# Morpheus_NDO_ANO.net
KiCad netlist of a schematic drawn in Altium Designer
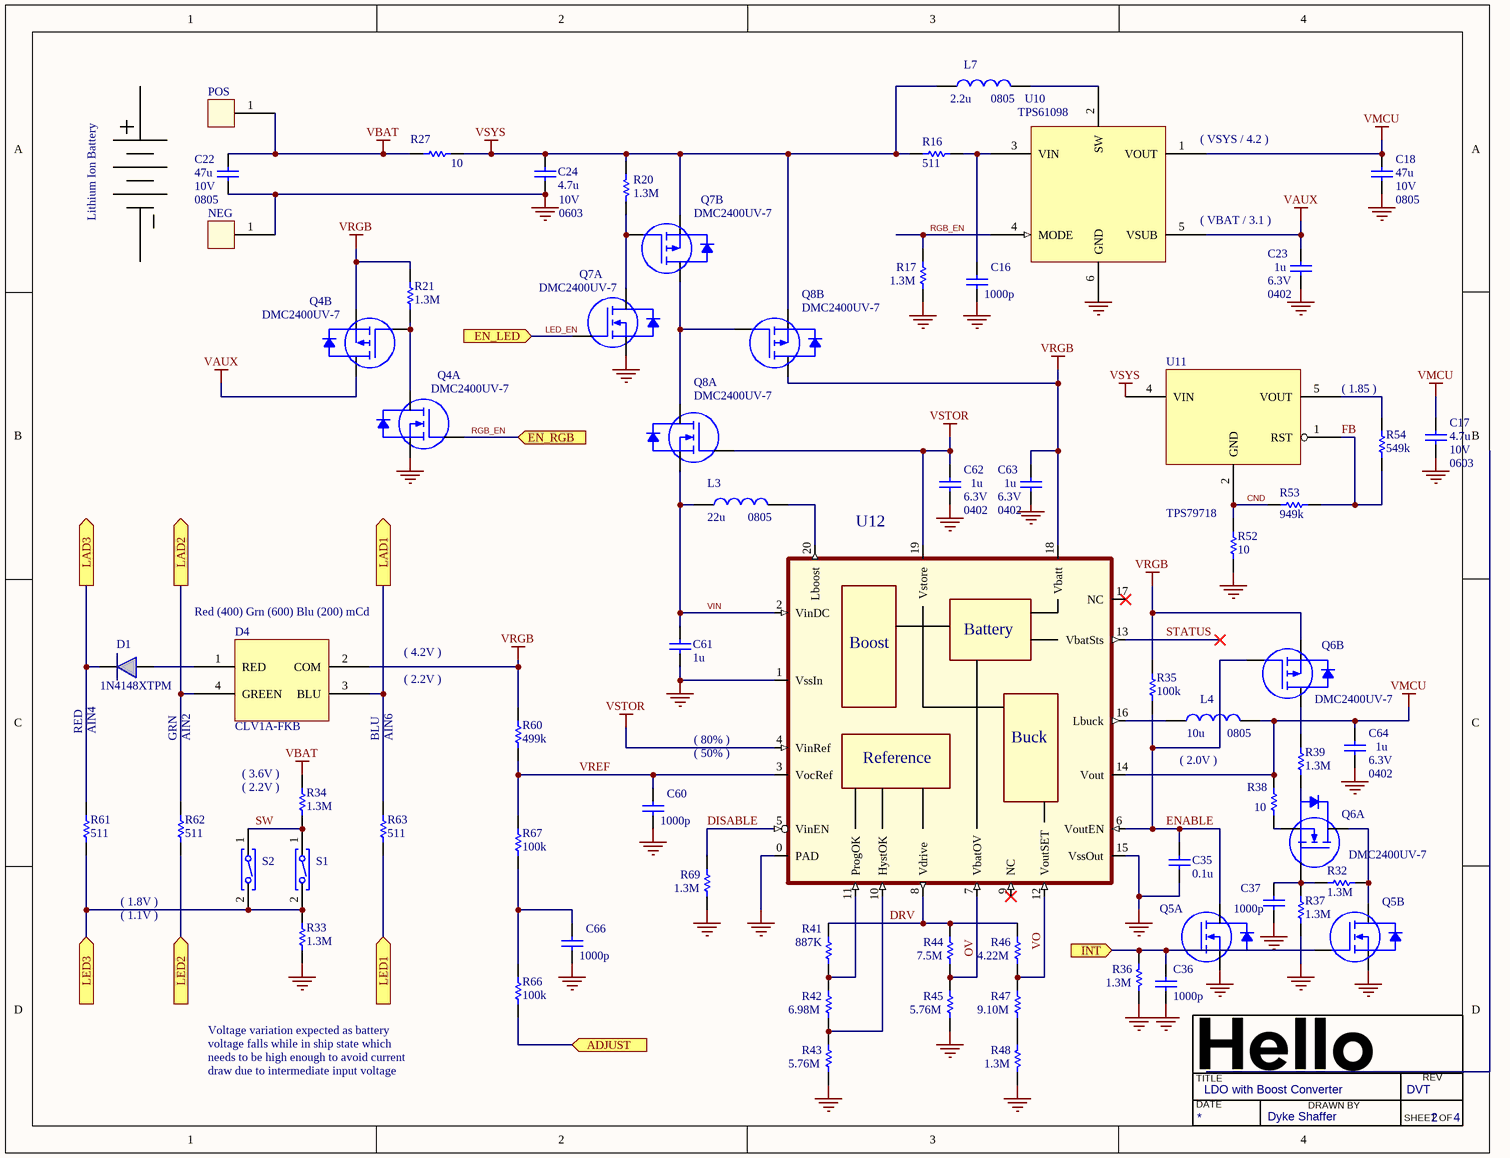
[diagram p0: Morpheus_NDO_ANO.SchDoc]

(export (version "E")
  (design (tool "Eeschema 10.0.6"))
  (components
    (comp (ref "C16")
      (value "1000p")
      (footprint "0402C20X24")
      (description "Chip capacitor")
      (fields (field (name "TOLERANCE") "10%") (field (name "VOLTAGE") "50V"))
      (libsource (lib "Hello") (part "C_1000p_10_50_X7R_0402"))
    )
    (comp (ref "C17")
      (value "4.7u")
      (footprint "CAP0603_SENSE_DVT")
      (description "Chip capacitor")
      (fields (field (name "SIZE") "0603") (field (name "TOLERANCE") "20%") (field (name "VOLTAGE") "10V"))
      (libsource (lib "Hello") (part "C_4.7u_20_10_X5R_0603"))
    )
    (comp (ref "C18")
      (value "47u")
      (footprint "0805C45X55")
      (description "Chip capacitor")
      (fields (field (name "SIZE") "0805") (field (name "TOLERANCE") "20%") (field (name "VOLTAGE") "10V"))
      (libsource (lib "Hello") (part "C_47u_20_10_X5R_0805"))
    )
    (comp (ref "C22")
      (value "47u")
      (footprint "CAP0805_SENSE_DVT")
      (description "Chip capacitor")
      (fields (field (name "SIZE") "0805") (field (name "TOLERANCE") "20%") (field (name "VOLTAGE") "10V"))
      (libsource (lib "Hello") (part "C_47u_20_10_X5R_0805"))
    )
    (comp (ref "C23")
      (value "1u")
      (footprint "CAP0402_SENSE_DVT")
      (description "Chip capacitor")
      (fields (field (name "SIZE") "0402") (field (name "TOLERANCE") "10%") (field (name "VOLTAGE") "6.3V"))
      (libsource (lib "Hello") (part "C_1u_10_6.3_X5R_0402"))
    )
    (comp (ref "C24")
      (value "4.7u")
      (footprint "CAP0603_SENSE_DVT")
      (description "Chip capacitor")
      (fields (field (name "SIZE") "0603") (field (name "TOLERANCE") "20%") (field (name "VOLTAGE") "10V"))
      (libsource (lib "Hello") (part "C_4.7u_20_10_X5R_0603"))
    )
    (comp (ref "C35")
      (value "0.1u")
      (footprint "CAP0402_SENSE_DVT")
      (description "Chip capacitor")
      (fields (field (name "TOLERANCE") "10%") (field (name "VOLTAGE") "50V"))
      (libsource (lib "Hello") (part "C_0.1u_10_50_X7R_0402"))
    )
    (comp (ref "C36")
      (value "1000p")
      (footprint "0402C20X24")
      (description "Chip capacitor")
      (fields (field (name "TOLERANCE") "10%") (field (name "VOLTAGE") "50V"))
      (libsource (lib "Hello") (part "C_1000p_10_50_X7R_0402"))
    )
    (comp (ref "C37")
      (value "1000p")
      (footprint "0402C20X24")
      (description "Chip capacitor")
      (fields (field (name "TOLERANCE") "10%") (field (name "VOLTAGE") "50V"))
      (libsource (lib "Hello") (part "C_1000p_10_50_X7R_0402"))
    )
    (comp (ref "C60")
      (value "1000p")
      (footprint "0402C20X24")
      (description "Chip capacitor")
      (fields (field (name "TOLERANCE") "10%") (field (name "VOLTAGE") "50V"))
      (libsource (lib "Hello") (part "C_1000p_10_50_X7R_0402"))
    )
    (comp (ref "C61")
      (value "1u")
      (footprint "CAP0402_SENSE_DVT")
      (description "Chip capacitor")
      (fields (field (name "TOLERANCE") "10%") (field (name "VOLTAGE") "6.3V"))
      (libsource (lib "Hello") (part "C_1u_10_6.3_X5R_0402"))
    )
    (comp (ref "C62")
      (value "1u")
      (footprint "CAP0402_SENSE_DVT")
      (description "Chip capacitor")
      (fields (field (name "SIZE") "0402") (field (name "TOLERANCE") "10%") (field (name "VOLTAGE") "6.3V"))
      (libsource (lib "Hello") (part "C_1u_10_6.3_X5R_0402"))
    )
    (comp (ref "C63")
      (value "1u")
      (footprint "CAP0402_SENSE_DVT")
      (description "Chip capacitor")
      (fields (field (name "SIZE") "0402") (field (name "TOLERANCE") "10%") (field (name "VOLTAGE") "6.3V"))
      (libsource (lib "Hello") (part "C_1u_10_6.3_X5R_0402"))
    )
    (comp (ref "C64")
      (value "1u")
      (footprint "CAP0402_SENSE_DVT")
      (description "Chip capacitor")
      (fields (field (name "SIZE") "0402") (field (name "TOLERANCE") "10%") (field (name "VOLTAGE") "6.3V"))
      (libsource (lib "Hello") (part "C_1u_10_6.3_X5R_0402"))
    )
    (comp (ref "C66")
      (value "1000p")
      (footprint "0402C20X24")
      (description "Chip capacitor")
      (fields (field (name "TOLERANCE") "10%") (field (name "VOLTAGE") "50V"))
      (libsource (lib "Hello") (part "C_1000p_10_50_X7R_0402"))
    )
    (comp (ref "D1")
      (value "1N4148XTPM")
      (footprint "SOD523")
      (description "Silicon diode, 30V 200mA")
      (libsource (lib "Hello") (part "1N4148XTPM"))
    )
    (comp (ref "D4")
      (value "Red (400) Grn (600) Blu (200) mCd")
      (footprint "PLCC150X290P280X320X190-4")
      (description "RGB LED Array")
      (fields (field (name "PN") "CLV1A-FKB") (field (name "Comment") "CLV1A-FKB"))
      (libsource (lib "Hello") (part "CLV1A-FKB"))
    )
    (comp (ref "L3")
      (value "22u")
      (footprint "IND_0805")
      (description "SMD power inductor, 22uH")
      (fields (field (name "TOLERANCE") "20%") (field (name "SIZE") "0805"))
      (libsource (lib "Morpheus_pill") (part "L_22u_0805"))
    )
    (comp (ref "L4")
      (value "10u")
      (footprint "IND_0805")
      (description "SMD power inductor, 10uH")
      (fields (field (name "TOLERANCE") "20%") (field (name "SIZE") "0805"))
      (libsource (lib "Morpheus_pill") (part "L_10u_0805"))
    )
    (comp (ref "L7")
      (value "2.2u")
      (footprint "IND_0805")
      (description "SMD power inductor, 2.2uH")
      (fields (field (name "TOLERANCE") "20%") (field (name "SIZE") "0805"))
      (libsource (lib "Morpheus_pill") (part "L_2.2u_0805"))
    )
    (comp (ref "NEG")
      (value "~")
      (footprint "TP50x50CP")
      (description "Single-pad test point")
      (libsource (lib "Mopd") (part "5016"))
    )
    (comp (ref "POS")
      (value "~")
      (footprint "TP50x50CP")
      (description "Single-pad test point")
      (libsource (lib "Mopd") (part "5016"))
    )
    (comp (ref "Q4")
      (value "DMC2400UV-7")
      (footprint "SOT-563")
      (description "Dual PN-Channel MOSFET 1.2v drive 20V 0.88A")
      (libsource (lib "") (part "DMC2400UV-7_1"))
    )
    (comp (ref "Q5")
      (value "DMG6301UDW-7")
      (footprint "SOT-563")
      (libsource (lib "Hello") (part "DMG6301UDW-7"))
    )
    (comp (ref "Q6")
      (value "DMC2400UV-7")
      (footprint "SOT-563")
      (description "Dual PN-Channel MOSFET 1.2v drive 20V 0.88A")
      (libsource (lib "Smith_bot") (part "DMC2400UV-7"))
    )
    (comp (ref "Q7")
      (value "DMC2400UV-7")
      (footprint "SOT-563")
      (description "Dual PN-Channel MOSFET 1.2v drive 20V 0.88A")
      (libsource (lib "Smith_bot") (part "DMC2400UV-7"))
    )
    (comp (ref "Q8")
      (value "DMC2400UV-7")
      (footprint "SOT-563")
      (description "Dual PN-Channel MOSFET 1.2v drive 20V 0.88A")
      (libsource (lib "Smith_bot") (part "DMC2400UV-7"))
    )
    (comp (ref "R16")
      (value "511")
      (footprint "RES0402_SENSE_DVT")
      (description "Chip Resistor")
      (fields (field (name "TOLERANCE") "1 %") (field (name "POWER") "0.1 W"))
      (libsource (lib "Hello") (part "R_511_1_0.1_0402"))
    )
    (comp (ref "R17")
      (value "1.3M")
      (footprint "RES0402_SENSE_DVT")
      (description "Chip Resistor")
      (fields (field (name "TOLERANCE") "5 %") (field (name "POWER") "0.1 W"))
      (libsource (lib "Hello") (part "R_1.3M_5_0.1_0402"))
    )
    (comp (ref "R20")
      (value "1.3M")
      (footprint "RES0402_SENSE_DVT")
      (description "Chip Resistor")
      (fields (field (name "TOLERANCE") "5 %") (field (name "POWER") "0.1 W"))
      (libsource (lib "Hello") (part "R_1.3M_5_0.1_0402"))
    )
    (comp (ref "R21")
      (value "1.3M")
      (footprint "RES0402_SENSE_DVT")
      (description "Chip Resistor")
      (fields (field (name "TOLERANCE") "5 %") (field (name "POWER") "0.1 W"))
      (libsource (lib "Hello") (part "R_1.3M_5_0.1_0402"))
    )
    (comp (ref "R27")
      (value "10")
      (footprint "RES0402_SENSE_DVT")
      (description "Chip Resistor")
      (fields (field (name "TOLERANCE") "1 %") (field (name "POWER") "0.1 W"))
      (libsource (lib "Hello") (part "R_10_1_0.1_0402"))
    )
    (comp (ref "R32")
      (value "1.3M")
      (footprint "RES0402_SENSE_DVT")
      (description "Chip Resistor")
      (fields (field (name "TOLERANCE") "5 %") (field (name "POWER") "0.1 W"))
      (libsource (lib "Hello") (part "R_1.3M_5_0.1_0402"))
    )
    (comp (ref "R33")
      (value "1.3M")
      (footprint "RES0402_SENSE_DVT")
      (description "Chip Resistor")
      (fields (field (name "TOLERANCE") "5 %") (field (name "POWER") "0.1 W"))
      (libsource (lib "Hello") (part "R_1.3M_5_0.1_0402"))
    )
    (comp (ref "R34")
      (value "1.3M")
      (footprint "RES0402_SENSE_DVT")
      (description "Chip Resistor")
      (fields (field (name "TOLERANCE") "5 %") (field (name "POWER") "0.1 W"))
      (libsource (lib "Hello") (part "R_1.3M_5_0.1_0402"))
    )
    (comp (ref "R35")
      (value "100k")
      (footprint "RES0402_SENSE_DVT")
      (description "Chip Resistor")
      (fields (field (name "TOLERANCE") "1 %") (field (name "POWER") "0.1 W"))
      (libsource (lib "Hello") (part "R_100k_1_0.1_0402"))
    )
    (comp (ref "R36")
      (value "1.3M")
      (footprint "RES0402_SENSE_DVT")
      (description "Chip Resistor")
      (fields (field (name "TOLERANCE") "5 %") (field (name "POWER") "0.1 W"))
      (libsource (lib "Hello") (part "R_1.3M_5_0.1_0402"))
    )
    (comp (ref "R37")
      (value "1.3M")
      (footprint "RES0402_SENSE_DVT")
      (description "Chip Resistor")
      (fields (field (name "TOLERANCE") "5 %") (field (name "POWER") "0.1 W"))
      (libsource (lib "Hello") (part "R_1.3M_5_0.1_0402"))
    )
    (comp (ref "R38")
      (value "10")
      (footprint "RES0402_SENSE_DVT")
      (description "Chip Resistor")
      (fields (field (name "TOLERANCE") "1 %") (field (name "POWER") "0.1 W"))
      (libsource (lib "Hello") (part "R_10_1_0.1_0402"))
    )
    (comp (ref "R39")
      (value "1.3M")
      (footprint "RES0402_SENSE_DVT")
      (description "Chip Resistor")
      (fields (field (name "TOLERANCE") "5 %") (field (name "POWER") "0.1 W"))
      (libsource (lib "Hello") (part "R_1.3M_5_0.1_0402"))
    )
    (comp (ref "R41")
      (value "887K")
      (footprint "0402R18X20")
      (description "Chip Resistor")
      (fields (field (name "TOLERANCE") "5 %") (field (name "POWER") "0.1 W"))
      (libsource (lib "Hello") (part "R_1.3M_5_0.1_0402"))
    )
    (comp (ref "R42")
      (value "6.98M")
      (footprint "0402R18X20")
      (description "Chip Resistor")
      (fields (field (name "TOLERANCE") "5 %") (field (name "POWER") "0.1 W"))
      (libsource (lib "Hello") (part "R_1.3M_5_0.1_0402"))
    )
    (comp (ref "R43")
      (value "5.76M")
      (footprint "0402R18X20")
      (description "Chip Resistor")
      (fields (field (name "TOLERANCE") "5 %") (field (name "POWER") "0.1 W"))
      (libsource (lib "Hello") (part "R_1.3M_5_0.1_0402"))
    )
    (comp (ref "R44")
      (value "7.5M")
      (footprint "0402R18X20")
      (description "Chip Resistor")
      (fields (field (name "TOLERANCE") "5 %") (field (name "POWER") "0.1 W"))
      (libsource (lib "Hello") (part "R_1.3M_5_0.1_0402"))
    )
    (comp (ref "R45")
      (value "5.76M")
      (footprint "0402R18X20")
      (description "Chip Resistor")
      (fields (field (name "TOLERANCE") "5 %") (field (name "POWER") "0.1 W"))
      (libsource (lib "Hello") (part "R_1.3M_5_0.1_0402"))
    )
    (comp (ref "R46")
      (value "4.22M")
      (footprint "0402R18X20")
      (description "Chip Resistor")
      (fields (field (name "TOLERANCE") "5 %") (field (name "POWER") "0.1 W"))
      (libsource (lib "Hello") (part "R_1.3M_5_0.1_0402"))
    )
    (comp (ref "R47")
      (value "9.10M")
      (footprint "0402R18X20")
      (description "Chip Resistor")
      (fields (field (name "TOLERANCE") "5 %") (field (name "POWER") "0.1 W"))
      (libsource (lib "Hello") (part "R_1.3M_5_0.1_0402"))
    )
    (comp (ref "R48")
      (value "1.3M")
      (footprint "RES0402_SENSE_DVT")
      (description "Chip Resistor")
      (fields (field (name "TOLERANCE") "5 %") (field (name "POWER") "0.1 W"))
      (libsource (lib "Hello") (part "R_1.3M_5_0.1_0402"))
    )
    (comp (ref "R52")
      (value "10")
      (footprint "RES0402_SENSE_DVT")
      (description "Chip Resistor")
      (fields (field (name "TOLERANCE") "1 %") (field (name "POWER") "0.1 W"))
      (libsource (lib "Hello") (part "R_10_1_0.1_0402"))
    )
    (comp (ref "R53")
      (value "949k")
      (footprint "RES0402")
      (description "Chip Resistor")
      (fields (field (name "TOLERANCE") "1 %") (field (name "POWER") "0.1 W"))
      (libsource (lib "Hello") (part "R_949k_1_0.1_0402"))
    )
    (comp (ref "R54")
      (value "549k")
      (footprint "RES0402")
      (description "Chip Resistor")
      (fields (field (name "TOLERANCE") "1 %") (field (name "POWER") "0.1 W"))
      (libsource (lib "Hello") (part "R_549k_1_0.1_0402"))
    )
    (comp (ref "R60")
      (value "499k")
      (footprint "RES0402_SENSE_DVT")
      (description "Chip Resistor")
      (fields (field (name "TOLERANCE") "1 %") (field (name "POWER") "0.1 W"))
      (libsource (lib "Hello") (part "R_499k_1_0.1_0402"))
    )
    (comp (ref "R61")
      (value "511")
      (footprint "RES0402_SENSE_DVT")
      (description "Chip Resistor")
      (fields (field (name "TOLERANCE") "1 %") (field (name "POWER") "0.1 W"))
      (libsource (lib "Hello") (part "R_511_1_0.1_0402"))
    )
    (comp (ref "R62")
      (value "511")
      (footprint "RES0402_SENSE_DVT")
      (description "Chip Resistor")
      (fields (field (name "TOLERANCE") "1 %") (field (name "POWER") "0.1 W"))
      (libsource (lib "Hello") (part "R_511_1_0.1_0402"))
    )
    (comp (ref "R63")
      (value "511")
      (footprint "RES0402_SENSE_DVT")
      (description "Chip Resistor")
      (fields (field (name "TOLERANCE") "1 %") (field (name "POWER") "0.1 W"))
      (libsource (lib "Hello") (part "R_511_1_0.1_0402"))
    )
    (comp (ref "R66")
      (value "100k")
      (footprint "RES0402_SENSE_DVT")
      (description "Chip Resistor")
      (fields (field (name "TOLERANCE") "1 %") (field (name "POWER") "0.1 W"))
      (libsource (lib "Hello") (part "R_100k_1_0.1_0402"))
    )
    (comp (ref "R67")
      (value "100k")
      (footprint "RES0402_SENSE_DVT")
      (description "Chip Resistor")
      (fields (field (name "TOLERANCE") "1 %") (field (name "POWER") "0.1 W"))
      (libsource (lib "Hello") (part "R_100k_1_0.1_0402"))
    )
    (comp (ref "R69")
      (value "1.3M")
      (footprint "0402R18X20")
      (description "Chip Resistor")
      (fields (field (name "TOLERANCE") "5 %") (field (name "POWER") "0.1 W"))
      (libsource (lib "Hello") (part "R_1.3M_5_0.1_0402"))
    )
    (comp (ref "S1")
      (value "REED_SPST_NO")
      (footprint "REED-10x1.8")
      (description "SWITCH REED SPST NO")
      (libsource (lib "Hello") (part "SW_REED_SPST_NO"))
    )
    (comp (ref "S2")
      (value "REED_SPST_NO")
      (footprint "PLCC350X400P450X450X65-4")
      (description "SWITCH REED SPST NO")
      (libsource (lib "Hello") (part "SW_REED_SPST_NO"))
    )
    (comp (ref "U10")
      (value "TPS61098")
      (footprint "DFN50P150X150X80-6N")
      (description "Boost Converter")
      (libsource (lib "Smith_bot") (part "TPS61098"))
    )
    (comp (ref "U11")
      (value "TPS79718")
      (footprint "SOT65P212X110-5N")
      (description "LDO 1.8V SC70-5")
      (libsource (lib "dykes") (part "TPS79718DCK"))
    )
    (comp (ref "U12")
      (value "BQ25570RGR")
      (footprint "VQFN50P-20")
      (libsource (lib "dykes") (part "BQ25570RGR"))
    )
  )
  (nets
    (net (code "1") (name "/ADJUST") (class "Default")
      (node (ref "R66") (pin "1") (pinfunction "1_1") (pintype "passive"))
    )
    (net (code "2") (name "/CND") (class "Default")
      (node (ref "R52") (pin "1") (pinfunction "1_1") (pintype "passive"))
      (node (ref "R53") (pin "1") (pinfunction "1_1") (pintype "passive"))
      (node (ref "U11") (pin "2") (pinfunction "GND_2") (pintype "power_in"))
    )
    (net (code "3") (name "/DISABLE") (class "Default")
      (node (ref "R69") (pin "2") (pinfunction "2_2") (pintype "passive"))
      (node (ref "U12") (pin "5") (pinfunction "VinEN_5") (pintype "input"))
    )
    (net (code "4") (name "/DRV") (class "Default")
      (node (ref "R41") (pin "2") (pinfunction "2_2") (pintype "passive"))
      (node (ref "R44") (pin "2") (pinfunction "2_2") (pintype "passive"))
      (node (ref "R46") (pin "2") (pinfunction "2_2") (pintype "passive"))
      (node (ref "U12") (pin "8") (pinfunction "Vdrive_8") (pintype "output"))
    )
    (net (code "5") (name "/ENABLE") (class "Default")
      (node (ref "C35") (pin "2") (pinfunction "2_2") (pintype "passive"))
      (node (ref "Q5") (pin "6") (pinfunction "D1_6") (pintype "passive"))
      (node (ref "Q6") (pin "5") (pinfunction "G2_5") (pintype "passive"))
      (node (ref "R35") (pin "1") (pinfunction "1_1") (pintype "passive"))
      (node (ref "U12") (pin "6") (pinfunction "VoutEN_6") (pintype "input"))
    )
    (net (code "6") (name "/FB") (class "Default")
      (node (ref "R53") (pin "2") (pinfunction "2_2") (pintype "passive"))
      (node (ref "R54") (pin "1") (pinfunction "1_1") (pintype "passive"))
      (node (ref "U11") (pin "1") (pinfunction "RST_1") (pintype "open_collector"))
    )
    (net (code "7") (name "/INT") (class "Default")
      (node (ref "C36") (pin "2") (pinfunction "2_2") (pintype "passive"))
      (node (ref "Q5") (pin "2") (pinfunction "G1_2") (pintype "passive"))
      (node (ref "Q5") (pin "5") (pinfunction "G2_5") (pintype "passive"))
      (node (ref "R36") (pin "2") (pinfunction "2_2") (pintype "passive"))
    )
    (net (code "8") (name "/LAD1") (class "Default")
      (node (ref "D4") (pin "3") (pinfunction "BLU_3") (pintype "passive"))
      (node (ref "R63") (pin "2") (pinfunction "2_2") (pintype "passive"))
    )
    (net (code "9") (name "/LAD2") (class "Default")
      (node (ref "D4") (pin "4") (pinfunction "GREEN_4") (pintype "passive"))
      (node (ref "R62") (pin "2") (pinfunction "2_2") (pintype "passive"))
    )
    (net (code "10") (name "/LAD3") (class "Default")
      (node (ref "D1") (pin "1") (pinfunction "Cathode_1") (pintype "passive"))
      (node (ref "R61") (pin "2") (pinfunction "2_2") (pintype "passive"))
    )
    (net (code "11") (name "/LED1") (class "Default")
      (node (ref "R63") (pin "1") (pinfunction "1_1") (pintype "passive"))
    )
    (net (code "12") (name "/LED2") (class "Default")
      (node (ref "R62") (pin "1") (pinfunction "1_1") (pintype "passive"))
    )
    (net (code "13") (name "/LED3") (class "Default")
      (node (ref "R33") (pin "2") (pinfunction "2_2") (pintype "passive"))
      (node (ref "R61") (pin "1") (pinfunction "1_1") (pintype "passive"))
      (node (ref "S1") (pin "2") (pinfunction "2_2") (pintype "passive"))
      (node (ref "S2") (pin "2") (pinfunction "2_2") (pintype "passive"))
    )
    (net (code "14") (name "/LED_EN") (class "Default")
      (node (ref "Q7") (pin "2") (pinfunction "G1_2") (pintype "passive"))
    )
    (net (code "15") (name "/OV") (class "Default")
      (node (ref "R44") (pin "1") (pinfunction "1_1") (pintype "passive"))
      (node (ref "R45") (pin "2") (pinfunction "2_2") (pintype "passive"))
      (node (ref "U12") (pin "7") (pinfunction "VbatOV_7") (pintype "input"))
    )
    (net (code "16") (name "/RGB_EN") (class "Default")
      (node (ref "Q4") (pin "2") (pinfunction "G1_2") (pintype "passive"))
      (node (ref "R17") (pin "1") (pinfunction "1_1") (pintype "passive"))
      (node (ref "U10") (pin "4") (pinfunction "MODE_4") (pintype "input"))
    )
    (net (code "17") (name "/STATUS") (class "Default")
      (node (ref "U12") (pin "13") (pinfunction "VbatSts_13") (pintype "output+no_connect"))
    )
    (net (code "18") (name "/SW") (class "Default")
      (node (ref "R34") (pin "1") (pinfunction "1_1") (pintype "passive"))
      (node (ref "S1") (pin "1") (pinfunction "1_1") (pintype "passive"))
      (node (ref "S2") (pin "1") (pinfunction "1_1") (pintype "passive"))
    )
    (net (code "19") (name "/VIN") (class "Default")
      (node (ref "C61") (pin "2") (pinfunction "2_2") (pintype "passive"))
      (node (ref "L3") (pin "2") (pintype "passive"))
      (node (ref "Q8") (pin "1") (pinfunction "S1_1") (pintype "passive"))
      (node (ref "U12") (pin "2") (pinfunction "VinDC_2") (pintype "input"))
    )
    (net (code "20") (name "/VO") (class "Default")
      (node (ref "R46") (pin "1") (pinfunction "1_1") (pintype "passive"))
      (node (ref "R47") (pin "2") (pinfunction "2_2") (pintype "passive"))
      (node (ref "U12") (pin "12") (pinfunction "VoutSET_12") (pintype "input"))
    )
    (net (code "21") (name "/VREF") (class "Default")
      (node (ref "C60") (pin "2") (pinfunction "2_2") (pintype "passive"))
      (node (ref "R60") (pin "1") (pinfunction "1_1") (pintype "passive"))
      (node (ref "R67") (pin "2") (pinfunction "2_2") (pintype "passive"))
      (node (ref "U12") (pin "3") (pinfunction "VocRef_3") (pintype "passive"))
    )
    (net (code "22") (name "GND") (class "Default")
      (node (ref "C16") (pin "1") (pinfunction "1_1") (pintype "passive"))
      (node (ref "C17") (pin "1") (pinfunction "1_1") (pintype "passive"))
      (node (ref "C18") (pin "1") (pinfunction "1_1") (pintype "passive"))
      (node (ref "C22") (pin "1") (pinfunction "1_1") (pintype "passive"))
      (node (ref "C23") (pin "1") (pinfunction "1_1") (pintype "passive"))
      (node (ref "C24") (pin "1") (pinfunction "1_1") (pintype "passive"))
      (node (ref "C35") (pin "1") (pinfunction "1_1") (pintype "passive"))
      (node (ref "C36") (pin "1") (pinfunction "1_1") (pintype "passive"))
      (node (ref "C37") (pin "1") (pinfunction "1_1") (pintype "passive"))
      (node (ref "C60") (pin "1") (pinfunction "1_1") (pintype "passive"))
      (node (ref "C61") (pin "1") (pinfunction "1_1") (pintype "passive"))
      (node (ref "C62") (pin "1") (pinfunction "1_1") (pintype "passive"))
      (node (ref "C64") (pin "1") (pinfunction "1_1") (pintype "passive"))
      (node (ref "C66") (pin "1") (pinfunction "1_1") (pintype "passive"))
      (node (ref "NEG") (pin "1") (pinfunction "1_1") (pintype "passive"))
      (node (ref "Q4") (pin "1") (pinfunction "S1_1") (pintype "passive"))
      (node (ref "Q5") (pin "1") (pinfunction "S1_1") (pintype "passive"))
      (node (ref "Q5") (pin "4") (pinfunction "S2_4") (pintype "passive"))
      (node (ref "Q7") (pin "1") (pinfunction "S1_1") (pintype "passive"))
      (node (ref "R17") (pin "2") (pinfunction "2_2") (pintype "passive"))
      (node (ref "R33") (pin "1") (pinfunction "1_1") (pintype "passive"))
      (node (ref "R36") (pin "1") (pinfunction "1_1") (pintype "passive"))
      (node (ref "R37") (pin "1") (pinfunction "1_1") (pintype "passive"))
      (node (ref "R43") (pin "1") (pinfunction "1_1") (pintype "passive"))
      (node (ref "R45") (pin "1") (pinfunction "1_1") (pintype "passive"))
      (node (ref "R48") (pin "1") (pinfunction "1_1") (pintype "passive"))
      (node (ref "R52") (pin "2") (pinfunction "2_2") (pintype "passive"))
      (node (ref "R69") (pin "1") (pinfunction "1_1") (pintype "passive"))
      (node (ref "U12") (pin "0") (pinfunction "PAD_0") (pintype "passive"))
      (node (ref "U12") (pin "1") (pinfunction "VssIn_1") (pintype "power_in"))
      (node (ref "U12") (pin "15") (pinfunction "VssOut_15") (pintype "power_in"))
    )
    (net (code "23") (name "Net-(C66-Pad2)") (class "Default")
      (node (ref "C66") (pin "2") (pinfunction "2_2") (pintype "passive"))
      (node (ref "R66") (pin "2") (pinfunction "2_2") (pintype "passive"))
      (node (ref "R67") (pin "1") (pinfunction "1_1") (pintype "passive"))
    )
    (net (code "24") (name "Net-(D1-Anode)") (class "Default")
      (node (ref "D1") (pin "2") (pinfunction "Anode_2") (pintype "passive"))
      (node (ref "D4") (pin "1") (pinfunction "RED_1") (pintype "passive"))
    )
    (net (code "25") (name "Net-(Q4A-D1)") (class "Default")
      (node (ref "Q4") (pin "5") (pinfunction "G2_5") (pintype "passive"))
      (node (ref "Q4") (pin "6") (pinfunction "D1_6") (pintype "passive"))
      (node (ref "R21") (pin "1") (pinfunction "1_1") (pintype "passive"))
    )
    (net (code "26") (name "Net-(Q5B-D2)") (class "Default")
      (node (ref "Q5") (pin "3") (pinfunction "D2_3") (pintype "passive"))
      (node (ref "Q6") (pin "6") (pinfunction "D1_6") (pintype "passive"))
      (node (ref "R32") (pin "1") (pinfunction "1_1") (pintype "passive"))
    )
    (net (code "27") (name "Net-(Q6A-G1)") (class "Default")
      (node (ref "C37") (pin "2") (pinfunction "2_2") (pintype "passive"))
      (node (ref "Q6") (pin "2") (pinfunction "G1_2") (pintype "passive"))
      (node (ref "R32") (pin "2") (pinfunction "2_2") (pintype "passive"))
      (node (ref "R37") (pin "2") (pinfunction "2_2") (pintype "passive"))
      (node (ref "R39") (pin "1") (pinfunction "1_1") (pintype "passive"))
    )
    (net (code "28") (name "Net-(Q6A-S1)") (class "Default")
      (node (ref "Q6") (pin "1") (pinfunction "S1_1") (pintype "passive"))
      (node (ref "R38") (pin "1") (pinfunction "1_1") (pintype "passive"))
    )
    (net (code "29") (name "Net-(Q6B-D2)") (class "Default")
      (node (ref "Q6") (pin "3") (pinfunction "D2_3") (pintype "passive"))
      (node (ref "R39") (pin "2") (pinfunction "2_2") (pintype "passive"))
    )
    (net (code "30") (name "Net-(Q7A-D1)") (class "Default")
      (node (ref "Q7") (pin "5") (pinfunction "G2_5") (pintype "passive"))
      (node (ref "Q7") (pin "6") (pinfunction "D1_6") (pintype "passive"))
      (node (ref "R20") (pin "1") (pinfunction "1_1") (pintype "passive"))
    )
    (net (code "31") (name "Net-(Q7B-D2)") (class "Default")
      (node (ref "Q7") (pin "3") (pinfunction "D2_3") (pintype "passive"))
      (node (ref "Q8") (pin "5") (pinfunction "G2_5") (pintype "passive"))
      (node (ref "Q8") (pin "6") (pinfunction "D1_6") (pintype "passive"))
    )
    (net (code "32") (name "Net-(R47-Pad1)") (class "Default")
      (node (ref "R47") (pin "1") (pinfunction "1_1") (pintype "passive"))
      (node (ref "R48") (pin "2") (pinfunction "2_2") (pintype "passive"))
    )
    (net (code "33") (name "Net-(U10-SW)") (class "Default")
      (node (ref "L7") (pin "1") (pintype "passive"))
      (node (ref "U10") (pin "2") (pinfunction "SW_2") (pintype "passive"))
    )
    (net (code "34") (name "Net-(U10-VIN)") (class "Default")
      (node (ref "C16") (pin "2") (pinfunction "2_2") (pintype "passive"))
      (node (ref "R16") (pin "1") (pinfunction "1_1") (pintype "passive"))
      (node (ref "U10") (pin "3") (pinfunction "VIN_3") (pintype "power_in"))
    )
    (net (code "35") (name "Net-(U11-VOUT)") (class "Default")
      (node (ref "R54") (pin "2") (pinfunction "2_2") (pintype "passive"))
      (node (ref "U11") (pin "5") (pinfunction "VOUT_5") (pintype "power_in"))
    )
    (net (code "36") (name "Net-(U12-HystOK)") (class "Default")
      (node (ref "R42") (pin "1") (pinfunction "1_1") (pintype "passive"))
      (node (ref "R43") (pin "2") (pinfunction "2_2") (pintype "passive"))
      (node (ref "U12") (pin "10") (pinfunction "HystOK_10") (pintype "input"))
    )
    (net (code "37") (name "Net-(U12-Lboost)") (class "Default")
      (node (ref "L3") (pin "1") (pintype "passive"))
      (node (ref "U12") (pin "20") (pinfunction "Lboost_20") (pintype "output"))
    )
    (net (code "38") (name "Net-(U12-Lbuck)") (class "Default")
      (node (ref "L4") (pin "2") (pintype "passive"))
      (node (ref "U12") (pin "16") (pinfunction "Lbuck_16") (pintype "output"))
    )
    (net (code "39") (name "Net-(U12-ProgOK)") (class "Default")
      (node (ref "R41") (pin "1") (pinfunction "1_1") (pintype "passive"))
      (node (ref "R42") (pin "2") (pinfunction "2_2") (pintype "passive"))
      (node (ref "U12") (pin "11") (pinfunction "ProgOK_11") (pintype "input"))
    )
    (net (code "40") (name "VAUX") (class "Default")
      (node (ref "C23") (pin "2") (pinfunction "2_2") (pintype "passive"))
      (node (ref "Q4") (pin "3") (pinfunction "D2_3") (pintype "passive"))
      (node (ref "U10") (pin "5") (pinfunction "VSUB_5") (pintype "power_in"))
    )
    (net (code "41") (name "VBAT") (class "Default")
      (node (ref "C22") (pin "2") (pinfunction "2_2") (pintype "passive"))
      (node (ref "POS") (pin "1") (pinfunction "1_1") (pintype "passive"))
      (node (ref "R27") (pin "1") (pinfunction "1_1") (pintype "passive"))
      (node (ref "R34") (pin "2") (pinfunction "2_2") (pintype "passive"))
    )
    (net (code "42") (name "VMCU") (class "Default")
      (node (ref "C17") (pin "2") (pinfunction "2_2") (pintype "passive"))
      (node (ref "C18") (pin "2") (pinfunction "2_2") (pintype "passive"))
      (node (ref "C64") (pin "2") (pinfunction "2_2") (pintype "passive"))
      (node (ref "L4") (pin "1") (pintype "passive"))
      (node (ref "R38") (pin "2") (pinfunction "2_2") (pintype "passive"))
      (node (ref "U10") (pin "1") (pinfunction "VOUT_1") (pintype "power_in"))
      (node (ref "U12") (pin "14") (pinfunction "Vout_14") (pintype "power_in"))
    )
    (net (code "43") (name "VRGB") (class "Default")
      (node (ref "C63") (pin "2") (pinfunction "2_2") (pintype "passive"))
      (node (ref "D4") (pin "2") (pinfunction "COM_2") (pintype "passive"))
      (node (ref "Q4") (pin "4") (pinfunction "S2_4") (pintype "passive"))
      (node (ref "Q6") (pin "4") (pinfunction "S2_4") (pintype "passive"))
      (node (ref "Q8") (pin "3") (pinfunction "D2_3") (pintype "passive"))
      (node (ref "R21") (pin "2") (pinfunction "2_2") (pintype "passive"))
      (node (ref "R35") (pin "2") (pinfunction "2_2") (pintype "passive"))
      (node (ref "R60") (pin "2") (pinfunction "2_2") (pintype "passive"))
      (node (ref "U12") (pin "18") (pinfunction "Vbatt_18") (pintype "power_in"))
    )
    (net (code "44") (name "VSTOR") (class "Default")
      (node (ref "C62") (pin "2") (pinfunction "2_2") (pintype "passive"))
      (node (ref "Q8") (pin "2") (pinfunction "G1_2") (pintype "passive"))
      (node (ref "U12") (pin "19") (pinfunction "Vstore_19") (pintype "power_in"))
      (node (ref "U12") (pin "4") (pinfunction "VinRef_4") (pintype "input"))
    )
    (net (code "45") (name "VSYS") (class "Default")
      (node (ref "C24") (pin "2") (pinfunction "2_2") (pintype "passive"))
      (node (ref "L7") (pin "2") (pintype "passive"))
      (node (ref "Q7") (pin "4") (pinfunction "S2_4") (pintype "passive"))
      (node (ref "Q8") (pin "4") (pinfunction "S2_4") (pintype "passive"))
      (node (ref "R16") (pin "2") (pinfunction "2_2") (pintype "passive"))
      (node (ref "R20") (pin "2") (pinfunction "2_2") (pintype "passive"))
      (node (ref "R27") (pin "2") (pinfunction "2_2") (pintype "passive"))
      (node (ref "U11") (pin "4") (pinfunction "VIN_4") (pintype "power_in"))
    )
    (net (code "46") (name "unconnected-(C63-Pad1)") (class "Default")
      (node (ref "C63") (pin "1") (pinfunction "1_1") (pintype "passive"))
    )
    (net (code "47") (name "unconnected-(U10-GND-Pad6)") (class "Default")
      (node (ref "U10") (pin "6") (pinfunction "GND_6") (pintype "power_in"))
    )
    (net (code "48") (name "unconnected-(U12-NC-Pad9)") (class "Default")
      (node (ref "U12") (pin "9") (pinfunction "NC_9") (pintype "input+no_connect"))
    )
    (net (code "49") (name "unconnected-(U12-NC-Pad17)") (class "Default")
      (node (ref "U12") (pin "17") (pinfunction "NC_17") (pintype "power_in+no_connect"))
    )
  )
)
